# MCU.net
KiCad netlist of a schematic drawn in Altium Designer
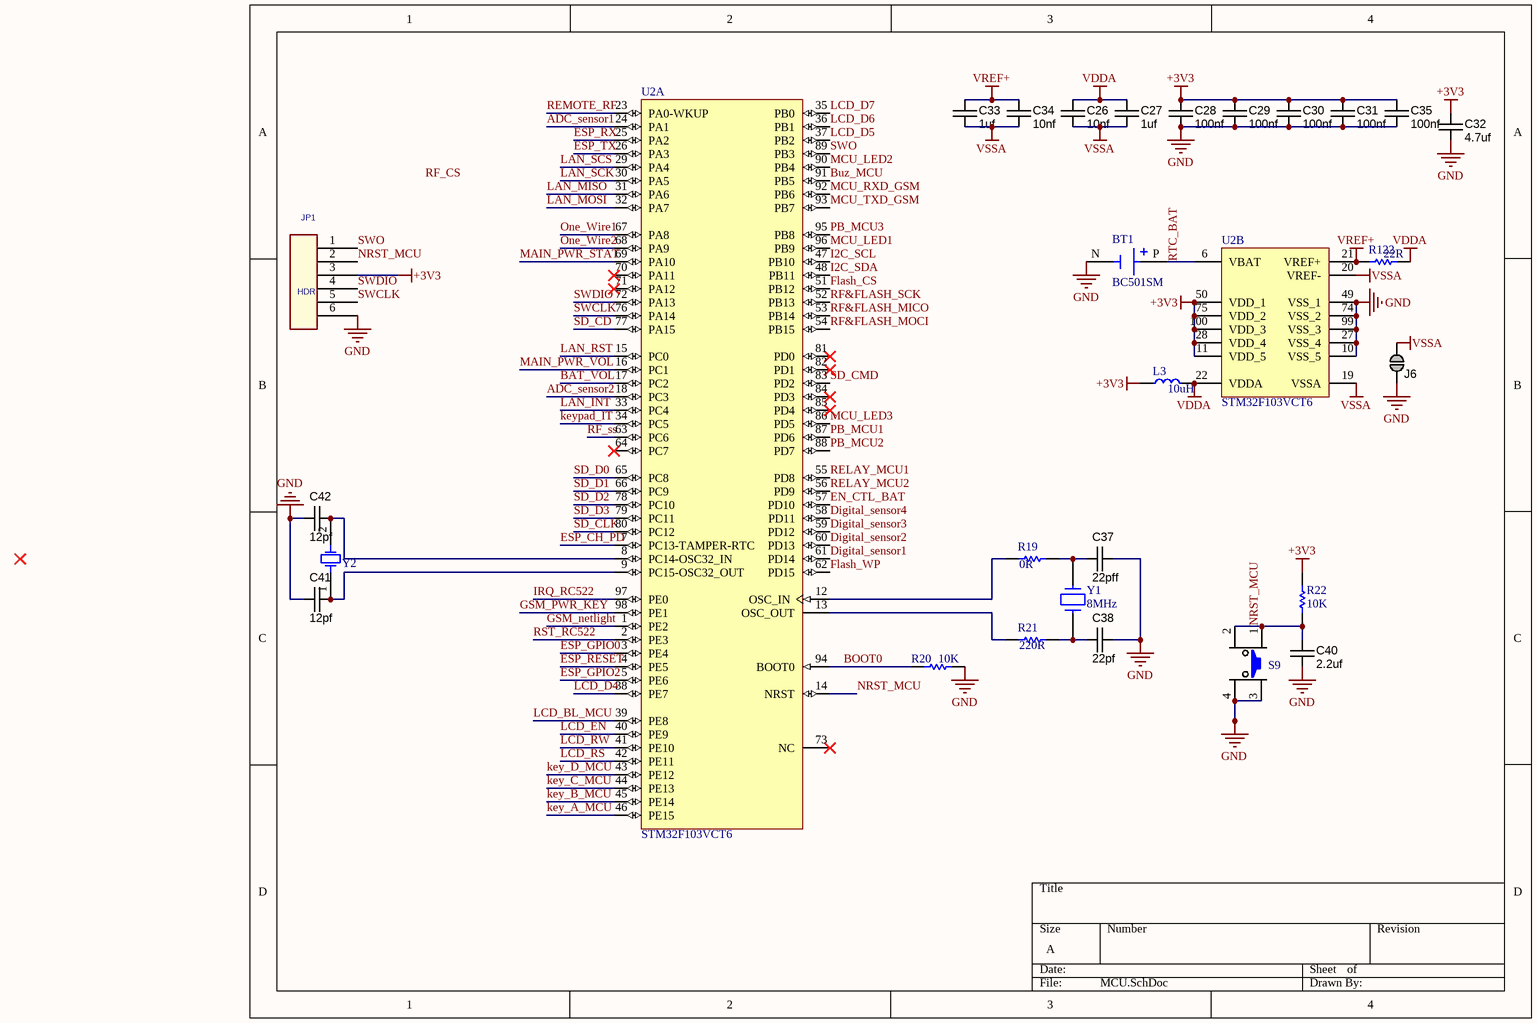
[diagram p0: MCU.SchDoc]

(export (version "E")
  (design (tool "Eeschema 10.0.6"))
  (components
    (comp (ref "BT1")
      (value "BC501SM")
      (footprint "BAT_BC501SM")
      (description "BATTERY HOLDER COIN 12MM SMD")
      (fields (field (name "MF") "MPD"))
      (libsource (lib "altium-import") (part "root_0_mirrored_BC501SM_"))
    )
    (comp (ref "C26")
      (value "10nf")
      (footprint "CAPC1608X90N")
      (description "Capacitor SMD Cer 100nF 10% 50V X7R 0603")
      (fields (field (name "TOLERANCE") "±10%"))
      (libsource (lib "altium-import") (part "root_2_CAPC_100n_0603_X7R_50V_10%_"))
    )
    (comp (ref "C27")
      (value "1uf")
      (footprint "CAPC1608X90N")
      (description "Capacitor SMD Cer 100nF 10% 50V X7R 0603")
      (fields (field (name "TOLERANCE") "±10%"))
      (libsource (lib "altium-import") (part "root_2_CAPC_100n_0603_X7R_50V_10%_"))
    )
    (comp (ref "C28")
      (value "100nf")
      (footprint "CAPC1608X90N")
      (description "Capacitor SMD Cer 100nF 10% 50V X7R 0603")
      (fields (field (name "TOLERANCE") "±10%"))
      (libsource (lib "altium-import") (part "root_2_CAPC_100n_0603_X7R_50V_10%_"))
    )
    (comp (ref "C29")
      (value "100nf")
      (footprint "CAPC1608X90N")
      (description "Capacitor SMD Cer 100nF 10% 50V X7R 0603")
      (fields (field (name "TOLERANCE") "±10%"))
      (libsource (lib "altium-import") (part "root_2_CAPC_100n_0603_X7R_50V_10%_"))
    )
    (comp (ref "C30")
      (value "100nf")
      (footprint "CAPC1608X90N")
      (description "Capacitor SMD Cer 100nF 10% 50V X7R 0603")
      (fields (field (name "TOLERANCE") "±10%"))
      (libsource (lib "altium-import") (part "root_2_CAPC_100n_0603_X7R_50V_10%_"))
    )
    (comp (ref "C31")
      (value "100nf")
      (footprint "CAPC1608X90N")
      (description "Capacitor SMD Cer 100nF 10% 50V X7R 0603")
      (fields (field (name "TOLERANCE") "±10%"))
      (libsource (lib "altium-import") (part "root_2_CAPC_100n_0603_X7R_50V_10%_"))
    )
    (comp (ref "C32")
      (value "4.7uf")
      (footprint "CAPC1608X90N")
      (description "Capacitor SMD Cer 100nF 10% 50V X7R 0603")
      (fields (field (name "TOLERANCE") "±10%"))
      (libsource (lib "altium-import") (part "root_2_CAPC_100n_0603_X7R_50V_10%_"))
    )
    (comp (ref "C33")
      (value "1uf")
      (footprint "CAPC1608X90N")
      (description "Capacitor SMD Cer 100nF 10% 50V X7R 0603")
      (fields (field (name "TOLERANCE") "±10%"))
      (libsource (lib "altium-import") (part "root_2_CAPC_100n_0603_X7R_50V_10%_"))
    )
    (comp (ref "C34")
      (value "10nf")
      (footprint "CAPC1608X90N")
      (description "Capacitor SMD Cer 100nF 10% 50V X7R 0603")
      (fields (field (name "TOLERANCE") "±10%"))
      (libsource (lib "altium-import") (part "root_2_CAPC_100n_0603_X7R_50V_10%_"))
    )
    (comp (ref "C35")
      (value "100nf")
      (footprint "CAPC1608X90N")
      (description "Capacitor SMD Cer 100nF 10% 50V X7R 0603")
      (fields (field (name "TOLERANCE") "±10%"))
      (libsource (lib "altium-import") (part "root_2_CAPC_100n_0603_X7R_50V_10%_"))
    )
    (comp (ref "C37")
      (value "22pff")
      (footprint "CAPC1608X90N")
      (description "Capacitor SMD Cer 100nF 10% 50V X7R 0603")
      (fields (field (name "TOLERANCE") "±10%"))
      (libsource (lib "altium-import") (part "root_1_CAPC_100n_0603_X7R_50V_10%_"))
    )
    (comp (ref "C38")
      (value "22pf")
      (footprint "CAPC1608X90N")
      (description "Capacitor SMD Cer 100nF 10% 50V X7R 0603")
      (fields (field (name "TOLERANCE") "±10%"))
      (libsource (lib "altium-import") (part "root_1_CAPC_100n_0603_X7R_50V_10%_"))
    )
    (comp (ref "C40")
      (value "2.2uf")
      (footprint "CAPC1608X90N")
      (description "Capacitor SMD Cer 100nF 10% 50V X7R 0603")
      (fields (field (name "TOLERANCE") "±10%"))
      (libsource (lib "altium-import") (part "root_0_CAPC_100n_0603_X7R_50V_10%_"))
    )
    (comp (ref "C41")
      (value "12pf")
      (footprint "CAPC1608X90N")
      (description "Capacitor SMD Cer 100nF 10% 50V X7R 0603")
      (fields (field (name "TOLERANCE") "±10%"))
      (libsource (lib "altium-import") (part "root_1_mirrored_CAPC_100n_0603_X7R_50V_10%_"))
    )
    (comp (ref "C42")
      (value "12pf")
      (footprint "CAPC1608X90N")
      (description "Capacitor SMD Cer 100nF 10% 50V X7R 0603")
      (fields (field (name "TOLERANCE") "±10%"))
      (libsource (lib "altium-import") (part "root_1_mirrored_CAPC_100n_0603_X7R_50V_10%_"))
    )
    (comp (ref "J6")
      (value "Jumper")
      (footprint "JUMP1")
      (description "SMD jumper")
      (libsource (lib "Utiliti_Library") (part "JUMP1"))
    )
    (comp (ref "JP1")
      (value "HDR")
      (footprint "HDR_1x6")
      (description "header or jumper box")
      (fields (field (name "DESIGNER") "ABBAS BASEREH"))
      (libsource (lib "altium-import") (part "root_0_mirrored_Header 1x6_"))
    )
    (comp (ref "L3")
      (value "10uH")
      (footprint "L0805")
      (description "Inductor SMD NC 0805")
      (libsource (lib "altium-import") (part "root_0_Inductor SMD NC 0805_"))
    )
    (comp (ref "R19")
      (value "0R")
      (footprint "Resistor_SMD_0603 (1608)")
      (description "Resistor 0603")
      (fields (field (name "PUBLISHER") "Seyed Razi Vesali") (field (name "EMAIL") "razi.vesali@gmail.com"))
      (libsource (lib "resistors") (part "Resistor"))
    )
    (comp (ref "R20")
      (value "10K")
      (footprint "Resistor_SMD_0603 (1608)")
      (description "Resistor 0603")
      (fields (field (name "PUBLISHER") "Seyed Razi Vesali") (field (name "EMAIL") "razi.vesali@gmail.com"))
      (libsource (lib "resistors") (part "Resistor"))
    )
    (comp (ref "R21")
      (value "220R")
      (footprint "Resistor_SMD_0603 (1608)")
      (description "Resistor 0603")
      (fields (field (name "PUBLISHER") "Seyed Razi Vesali") (field (name "EMAIL") "razi.vesali@gmail.com"))
      (libsource (lib "resistors") (part "Resistor"))
    )
    (comp (ref "R22")
      (value "10K")
      (footprint "Resistor_SMD_0603 (1608)")
      (description "Resistor 0603")
      (fields (field (name "PUBLISHER") "Seyed Razi Vesali") (field (name "EMAIL") "razi.vesali@gmail.com"))
      (libsource (lib "resistors") (part "Resistor"))
    )
    (comp (ref "R122")
      (value "22R")
      (footprint "Resistor_SMD_0603 (1608)")
      (description "Resistor 0603")
      (fields (field (name "PUBLISHER") "Seyed Razi Vesali") (field (name "EMAIL") "razi.vesali@gmail.com"))
      (libsource (lib "resistors") (part "Resistor"))
    )
    (comp (ref "S9")
      (value "SW_PB4 SMD")
      (footprint "SMD_PB")
      (libsource (lib "Micro Switch") (part "SW_PB4 SMD"))
    )
    (comp (ref "U2")
      (value "STM32F103VCT6")
      (footprint "STM-LQFP100_L")
      (libsource (lib "altium-import") (part "root_0_STM32F103VCT6_"))
    )
    (comp (ref "Y1")
      (value "8MHz")
      (footprint "My_Crystal - SMD")
      (description "Crystal")
      (libsource (lib "altium-import") (part "root_1_CRYSTAL_SMD_"))
    )
    (comp (ref "Y2")
      (value "32.768KHz")
      (footprint "Crystal Clock RIGHT 3")
      (description "Crystal")
      (libsource (lib "altium-import") (part "root_1_mirrored_Crystal RTC_"))
    )
  )
  (nets
    (net (code "1") (name "+3V3") (class "Default")
      (node (ref "C28") (pin "2") (pintype "passive"))
      (node (ref "C29") (pin "2") (pintype "passive"))
      (node (ref "C30") (pin "2") (pintype "passive"))
      (node (ref "C31") (pin "2") (pintype "passive"))
      (node (ref "C32") (pin "2") (pintype "passive"))
      (node (ref "C35") (pin "2") (pintype "passive"))
      (node (ref "JP1") (pin "3") (pinfunction "3_3") (pintype "passive"))
      (node (ref "L3") (pin "1") (pinfunction "1_1") (pintype "passive"))
      (node (ref "R22") (pin "1") (pinfunction "1_1") (pintype "passive"))
      (node (ref "U2") (pin "100") (pinfunction "VDD_3_100") (pintype "power_in"))
      (node (ref "U2") (pin "11") (pinfunction "VDD_5_11") (pintype "power_in"))
      (node (ref "U2") (pin "28") (pinfunction "VDD_4_28") (pintype "power_in"))
      (node (ref "U2") (pin "50") (pinfunction "VDD_1_50") (pintype "power_in"))
      (node (ref "U2") (pin "75") (pinfunction "VDD_2_75") (pintype "power_in"))
    )
    (net (code "2") (name "/ADC_sensor1") (class "Default")
      (node (ref "U2") (pin "24") (pinfunction "PA1_24") (pintype "bidirectional"))
    )
    (net (code "3") (name "/ADC_sensor2") (class "Default")
      (node (ref "U2") (pin "18") (pinfunction "PC3_18") (pintype "bidirectional"))
    )
    (net (code "4") (name "/BAT_VOL") (class "Default")
      (node (ref "U2") (pin "17") (pinfunction "PC2_17") (pintype "bidirectional"))
    )
    (net (code "5") (name "/BOOT0") (class "Default")
      (node (ref "R20") (pin "1") (pinfunction "1_1") (pintype "passive"))
      (node (ref "U2") (pin "94") (pinfunction "BOOT0_94") (pintype "input"))
    )
    (net (code "6") (name "/Buz_MCU") (class "Default")
      (node (ref "U2") (pin "91") (pinfunction "PB5_91") (pintype "bidirectional"))
    )
    (net (code "7") (name "/Digital_sensor1") (class "Default")
      (node (ref "U2") (pin "61") (pinfunction "PD14_61") (pintype "bidirectional"))
    )
    (net (code "8") (name "/Digital_sensor2") (class "Default")
      (node (ref "U2") (pin "60") (pinfunction "PD13_60") (pintype "bidirectional"))
    )
    (net (code "9") (name "/Digital_sensor3") (class "Default")
      (node (ref "U2") (pin "59") (pinfunction "PD12_59") (pintype "bidirectional"))
    )
    (net (code "10") (name "/Digital_sensor4") (class "Default")
      (node (ref "U2") (pin "58") (pinfunction "PD11_58") (pintype "bidirectional"))
    )
    (net (code "11") (name "/EN_CTL_BAT") (class "Default")
      (node (ref "U2") (pin "57") (pinfunction "PD10_57") (pintype "bidirectional"))
    )
    (net (code "12") (name "/ESP_CH_PD") (class "Default")
      (node (ref "U2") (pin "7") (pinfunction "PC13-TAMPER-RTC_7") (pintype "bidirectional"))
    )
    (net (code "13") (name "/ESP_GPIO0") (class "Default")
      (node (ref "U2") (pin "3") (pinfunction "PE4_3") (pintype "bidirectional"))
    )
    (net (code "14") (name "/ESP_GPIO2") (class "Default")
      (node (ref "U2") (pin "5") (pinfunction "PE6_5") (pintype "bidirectional"))
    )
    (net (code "15") (name "/ESP_RESET") (class "Default")
      (node (ref "U2") (pin "4") (pinfunction "PE5_4") (pintype "bidirectional"))
    )
    (net (code "16") (name "/ESP_RX") (class "Default")
      (node (ref "U2") (pin "25") (pinfunction "PA2_25") (pintype "bidirectional"))
    )
    (net (code "17") (name "/ESP_TX") (class "Default")
      (node (ref "U2") (pin "26") (pinfunction "PA3_26") (pintype "bidirectional"))
    )
    (net (code "18") (name "/Flash_CS") (class "Default")
      (node (ref "U2") (pin "51") (pinfunction "PB12_51") (pintype "bidirectional"))
    )
    (net (code "19") (name "/Flash_WP") (class "Default")
      (node (ref "U2") (pin "62") (pinfunction "PD15_62") (pintype "bidirectional"))
    )
    (net (code "20") (name "/GSM_PWR_KEY") (class "Default")
      (node (ref "U2") (pin "98") (pinfunction "PE1_98") (pintype "bidirectional"))
    )
    (net (code "21") (name "/GSM_netlight") (class "Default")
      (node (ref "U2") (pin "1") (pinfunction "PE2_1") (pintype "bidirectional"))
    )
    (net (code "22") (name "/I2C_SCL") (class "Default")
      (node (ref "U2") (pin "47") (pinfunction "PB10_47") (pintype "bidirectional"))
    )
    (net (code "23") (name "/I2C_SDA") (class "Default")
      (node (ref "U2") (pin "48") (pinfunction "PB11_48") (pintype "bidirectional"))
    )
    (net (code "24") (name "/IRQ_RC522") (class "Default")
      (node (ref "U2") (pin "97") (pinfunction "PE0_97") (pintype "bidirectional"))
    )
    (net (code "25") (name "/LAN_INT") (class "Default")
      (node (ref "U2") (pin "33") (pinfunction "PC4_33") (pintype "bidirectional"))
    )
    (net (code "26") (name "/LAN_MISO") (class "Default")
      (node (ref "U2") (pin "31") (pinfunction "PA6_31") (pintype "bidirectional"))
    )
    (net (code "27") (name "/LAN_MOSI") (class "Default")
      (node (ref "U2") (pin "32") (pinfunction "PA7_32") (pintype "bidirectional"))
    )
    (net (code "28") (name "/LAN_RST") (class "Default")
      (node (ref "U2") (pin "15") (pinfunction "PC0_15") (pintype "bidirectional"))
    )
    (net (code "29") (name "/LAN_SCK") (class "Default")
      (node (ref "U2") (pin "30") (pinfunction "PA5_30") (pintype "bidirectional"))
    )
    (net (code "30") (name "/LAN_SCS") (class "Default")
      (node (ref "U2") (pin "29") (pinfunction "PA4_29") (pintype "bidirectional"))
    )
    (net (code "31") (name "/LCD_BL_MCU") (class "Default")
      (node (ref "U2") (pin "39") (pinfunction "PE8_39") (pintype "bidirectional"))
    )
    (net (code "32") (name "/LCD_D4") (class "Default")
      (node (ref "U2") (pin "38") (pinfunction "PE7_38") (pintype "bidirectional"))
    )
    (net (code "33") (name "/LCD_D5") (class "Default")
      (node (ref "U2") (pin "37") (pinfunction "PB2_37") (pintype "bidirectional"))
    )
    (net (code "34") (name "/LCD_D6") (class "Default")
      (node (ref "U2") (pin "36") (pinfunction "PB1_36") (pintype "bidirectional"))
    )
    (net (code "35") (name "/LCD_D7") (class "Default")
      (node (ref "U2") (pin "35") (pinfunction "PB0_35") (pintype "bidirectional"))
    )
    (net (code "36") (name "/LCD_EN") (class "Default")
      (node (ref "U2") (pin "40") (pinfunction "PE9_40") (pintype "bidirectional"))
    )
    (net (code "37") (name "/LCD_RS") (class "Default")
      (node (ref "U2") (pin "42") (pinfunction "PE11_42") (pintype "bidirectional"))
    )
    (net (code "38") (name "/LCD_RW") (class "Default")
      (node (ref "U2") (pin "41") (pinfunction "PE10_41") (pintype "bidirectional"))
    )
    (net (code "39") (name "/MAIN_PWR_STAT") (class "Default")
      (node (ref "U2") (pin "69") (pinfunction "PA10_69") (pintype "bidirectional"))
    )
    (net (code "40") (name "/MAIN_PWR_VOL") (class "Default")
      (node (ref "U2") (pin "16") (pinfunction "PC1_16") (pintype "bidirectional"))
    )
    (net (code "41") (name "/MCU_LED1") (class "Default")
      (node (ref "U2") (pin "96") (pinfunction "PB9_96") (pintype "bidirectional"))
    )
    (net (code "42") (name "/MCU_LED2") (class "Default")
      (node (ref "U2") (pin "90") (pinfunction "PB4_90") (pintype "bidirectional"))
    )
    (net (code "43") (name "/MCU_LED3") (class "Default")
      (node (ref "U2") (pin "86") (pinfunction "PD5_86") (pintype "bidirectional"))
    )
    (net (code "44") (name "/MCU_RXD_GSM") (class "Default")
      (node (ref "U2") (pin "92") (pinfunction "PB6_92") (pintype "bidirectional"))
    )
    (net (code "45") (name "/MCU_TXD_GSM") (class "Default")
      (node (ref "U2") (pin "93") (pinfunction "PB7_93") (pintype "bidirectional"))
    )
    (net (code "46") (name "/NRST_MCU") (class "Default")
      (node (ref "C40") (pin "1") (pintype "passive"))
      (node (ref "JP1") (pin "2") (pinfunction "2_2") (pintype "passive"))
      (node (ref "R22") (pin "2") (pinfunction "2_2") (pintype "passive"))
      (node (ref "S9") (pin "1") (pinfunction "1_1") (pintype "passive"))
      (node (ref "S9") (pin "2") (pinfunction "2_2") (pintype "passive"))
      (node (ref "U2") (pin "14") (pinfunction "NRST_14") (pintype "bidirectional"))
    )
    (net (code "47") (name "/One_Wire1") (class "Default")
      (node (ref "U2") (pin "67") (pinfunction "PA8_67") (pintype "bidirectional"))
    )
    (net (code "48") (name "/One_Wire2") (class "Default")
      (node (ref "U2") (pin "68") (pinfunction "PA9_68") (pintype "bidirectional"))
    )
    (net (code "49") (name "/PB_MCU1") (class "Default")
      (node (ref "U2") (pin "87") (pinfunction "PD6_87") (pintype "bidirectional"))
    )
    (net (code "50") (name "/PB_MCU2") (class "Default")
      (node (ref "U2") (pin "88") (pinfunction "PD7_88") (pintype "bidirectional"))
    )
    (net (code "51") (name "/PB_MCU3") (class "Default")
      (node (ref "U2") (pin "95") (pinfunction "PB8_95") (pintype "bidirectional"))
    )
    (net (code "52") (name "/RELAY_MCU1") (class "Default")
      (node (ref "U2") (pin "55") (pinfunction "PD8_55") (pintype "bidirectional"))
    )
    (net (code "53") (name "/RELAY_MCU2") (class "Default")
      (node (ref "U2") (pin "56") (pinfunction "PD9_56") (pintype "bidirectional"))
    )
    (net (code "54") (name "/REMOTE_RF") (class "Default")
      (node (ref "U2") (pin "23") (pinfunction "PA0-WKUP_23") (pintype "bidirectional"))
    )
    (net (code "55") (name "/RF&FLASH_MICO") (class "Default")
      (node (ref "U2") (pin "53") (pinfunction "PB14_53") (pintype "bidirectional"))
    )
    (net (code "56") (name "/RF&FLASH_MOCI") (class "Default")
      (node (ref "U2") (pin "54") (pinfunction "PB15_54") (pintype "bidirectional"))
    )
    (net (code "57") (name "/RF&FLASH_SCK") (class "Default")
      (node (ref "U2") (pin "52") (pinfunction "PB13_52") (pintype "bidirectional"))
    )
    (net (code "59") (name "/RF_ss") (class "Default")
      (node (ref "U2") (pin "63") (pinfunction "PC6_63") (pintype "bidirectional"))
    )
    (net (code "60") (name "/RST_RC522") (class "Default")
      (node (ref "U2") (pin "2") (pinfunction "PE3_2") (pintype "bidirectional"))
    )
    (net (code "61") (name "/RTC_BAT") (class "Default")
      (node (ref "BT1") (pin "P") (pinfunction "POS_P") (pintype "passive"))
      (node (ref "U2") (pin "6") (pinfunction "VBAT_6") (pintype "power_in"))
    )
    (net (code "62") (name "/SD_CD") (class "Default")
      (node (ref "U2") (pin "77") (pinfunction "PA15_77") (pintype "bidirectional"))
    )
    (net (code "63") (name "/SD_CLK") (class "Default")
      (node (ref "U2") (pin "80") (pinfunction "PC12_80") (pintype "bidirectional"))
    )
    (net (code "64") (name "/SD_CMD") (class "Default")
      (node (ref "U2") (pin "83") (pinfunction "PD2_83") (pintype "bidirectional"))
    )
    (net (code "65") (name "/SD_D0") (class "Default")
      (node (ref "U2") (pin "65") (pinfunction "PC8_65") (pintype "bidirectional"))
    )
    (net (code "66") (name "/SD_D1") (class "Default")
      (node (ref "U2") (pin "66") (pinfunction "PC9_66") (pintype "bidirectional"))
    )
    (net (code "67") (name "/SD_D2") (class "Default")
      (node (ref "U2") (pin "78") (pinfunction "PC10_78") (pintype "bidirectional"))
    )
    (net (code "68") (name "/SD_D3") (class "Default")
      (node (ref "U2") (pin "79") (pinfunction "PC11_79") (pintype "bidirectional"))
    )
    (net (code "69") (name "/SWCLK") (class "Default")
      (node (ref "JP1") (pin "5") (pinfunction "5_5") (pintype "passive"))
      (node (ref "U2") (pin "76") (pinfunction "PA14_76") (pintype "bidirectional"))
    )
    (net (code "70") (name "/SWDIO") (class "Default")
      (node (ref "JP1") (pin "4") (pinfunction "4_4") (pintype "passive"))
      (node (ref "U2") (pin "72") (pinfunction "PA13_72") (pintype "bidirectional"))
    )
    (net (code "71") (name "/SWO") (class "Default")
      (node (ref "JP1") (pin "1") (pinfunction "1_1") (pintype "passive"))
      (node (ref "U2") (pin "89") (pinfunction "PB3_89") (pintype "bidirectional"))
    )
    (net (code "72") (name "/key_A_MCU") (class "Default")
      (node (ref "U2") (pin "46") (pinfunction "PE15_46") (pintype "bidirectional"))
    )
    (net (code "73") (name "/key_B_MCU") (class "Default")
      (node (ref "U2") (pin "45") (pinfunction "PE14_45") (pintype "bidirectional"))
    )
    (net (code "74") (name "/key_C_MCU") (class "Default")
      (node (ref "U2") (pin "44") (pinfunction "PE13_44") (pintype "bidirectional"))
    )
    (net (code "75") (name "/key_D_MCU") (class "Default")
      (node (ref "U2") (pin "43") (pinfunction "PE12_43") (pintype "bidirectional"))
    )
    (net (code "76") (name "/keypad_IT") (class "Default")
      (node (ref "U2") (pin "34") (pinfunction "PC5_34") (pintype "bidirectional"))
    )
    (net (code "77") (name "GND") (class "Default")
      (node (ref "BT1") (pin "N") (pinfunction "NEG_N") (pintype "passive"))
      (node (ref "C28") (pin "1") (pintype "passive"))
      (node (ref "C29") (pin "1") (pintype "passive"))
      (node (ref "C30") (pin "1") (pintype "passive"))
      (node (ref "C31") (pin "1") (pintype "passive"))
      (node (ref "C32") (pin "1") (pintype "passive"))
      (node (ref "C35") (pin "1") (pintype "passive"))
      (node (ref "C37") (pin "2") (pintype "passive"))
      (node (ref "C38") (pin "2") (pintype "passive"))
      (node (ref "C40") (pin "2") (pintype "passive"))
      (node (ref "C41") (pin "2") (pintype "passive"))
      (node (ref "C42") (pin "2") (pintype "passive"))
      (node (ref "J6") (pin "1") (pintype "passive"))
      (node (ref "JP1") (pin "6") (pinfunction "6_6") (pintype "passive"))
      (node (ref "R20") (pin "2") (pinfunction "2_2") (pintype "passive"))
      (node (ref "S9") (pin "3") (pinfunction "3_3") (pintype "passive"))
      (node (ref "S9") (pin "4") (pinfunction "4_4") (pintype "passive"))
      (node (ref "U2") (pin "10") (pinfunction "VSS_5_10") (pintype "power_in"))
      (node (ref "U2") (pin "27") (pinfunction "VSS_4_27") (pintype "power_in"))
      (node (ref "U2") (pin "49") (pinfunction "VSS_1_49") (pintype "power_in"))
      (node (ref "U2") (pin "74") (pinfunction "VSS_2_74") (pintype "power_in"))
      (node (ref "U2") (pin "99") (pinfunction "VSS_3_99") (pintype "power_in"))
    )
    (net (code "78") (name "Net-(C37-Pad1)") (class "Default")
      (node (ref "C37") (pin "1") (pintype "passive"))
      (node (ref "R19") (pin "2") (pinfunction "2_2") (pintype "passive"))
      (node (ref "Y1") (pin "2") (pinfunction "2_2") (pintype "passive"))
    )
    (net (code "79") (name "Net-(C38-Pad1)") (class "Default")
      (node (ref "C38") (pin "1") (pintype "passive"))
      (node (ref "R21") (pin "2") (pinfunction "2_2") (pintype "passive"))
      (node (ref "Y1") (pin "1") (pinfunction "1_1") (pintype "passive"))
    )
    (net (code "80") (name "Net-(U2A-OSC_IN)") (class "Default")
      (node (ref "R19") (pin "1") (pinfunction "1_1") (pintype "passive"))
      (node (ref "U2") (pin "12") (pinfunction "OSC_IN_12") (pintype "input"))
    )
    (net (code "81") (name "Net-(U2A-OSC_OUT)") (class "Default")
      (node (ref "R21") (pin "1") (pinfunction "1_1") (pintype "passive"))
      (node (ref "U2") (pin "13") (pinfunction "OSC_OUT_13") (pintype "passive"))
    )
    (net (code "82") (name "Net-(U2A-PC14-OSC32_IN)") (class "Default")
      (node (ref "C42") (pin "1") (pintype "passive"))
      (node (ref "U2") (pin "8") (pinfunction "PC14-OSC32_IN_8") (pintype "bidirectional"))
      (node (ref "Y2") (pin "2") (pinfunction "2_2") (pintype "passive"))
    )
    (net (code "83") (name "Net-(U2A-PC15-OSC32_OUT)") (class "Default")
      (node (ref "C41") (pin "1") (pintype "passive"))
      (node (ref "U2") (pin "9") (pinfunction "PC15-OSC32_OUT_9") (pintype "bidirectional"))
      (node (ref "Y2") (pin "1") (pinfunction "1_1") (pintype "passive"))
    )
    (net (code "84") (name "VDDA") (class "Default")
      (node (ref "C26") (pin "2") (pintype "passive"))
      (node (ref "C27") (pin "2") (pintype "passive"))
      (node (ref "L3") (pin "2") (pinfunction "2_2") (pintype "passive"))
      (node (ref "R122") (pin "1") (pinfunction "1_1") (pintype "passive"))
      (node (ref "U2") (pin "22") (pinfunction "VDDA_22") (pintype "power_in"))
    )
    (net (code "85") (name "VREF+") (class "Default")
      (node (ref "C33") (pin "2") (pintype "passive"))
      (node (ref "C34") (pin "2") (pintype "passive"))
      (node (ref "R122") (pin "2") (pinfunction "2_2") (pintype "passive"))
      (node (ref "U2") (pin "21") (pinfunction "VREF+_21") (pintype "power_in"))
    )
    (net (code "86") (name "VSSA") (class "Default")
      (node (ref "C26") (pin "1") (pintype "passive"))
      (node (ref "C27") (pin "1") (pintype "passive"))
      (node (ref "C33") (pin "1") (pintype "passive"))
      (node (ref "C34") (pin "1") (pintype "passive"))
      (node (ref "J6") (pin "2") (pintype "passive"))
      (node (ref "U2") (pin "19") (pinfunction "VSSA_19") (pintype "power_in"))
      (node (ref "U2") (pin "20") (pinfunction "VREF-_20") (pintype "power_in"))
    )
    (net (code "87") (name "unconnected-(U2A-NC-Pad73)") (class "Default")
      (node (ref "U2") (pin "73") (pinfunction "NC_73") (pintype "passive+no_connect"))
    )
    (net (code "88") (name "unconnected-(U2A-PA11-Pad70)") (class "Default")
      (node (ref "U2") (pin "70") (pinfunction "PA11_70") (pintype "bidirectional+no_connect"))
    )
    (net (code "89") (name "unconnected-(U2A-PA12-Pad71)") (class "Default")
      (node (ref "U2") (pin "71") (pinfunction "PA12_71") (pintype "bidirectional+no_connect"))
    )
    (net (code "90") (name "unconnected-(U2A-PC7-Pad64)") (class "Default")
      (node (ref "U2") (pin "64") (pinfunction "PC7_64") (pintype "bidirectional+no_connect"))
    )
    (net (code "91") (name "unconnected-(U2A-PD0-Pad81)") (class "Default")
      (node (ref "U2") (pin "81") (pinfunction "PD0_81") (pintype "bidirectional+no_connect"))
    )
    (net (code "92") (name "unconnected-(U2A-PD1-Pad82)") (class "Default")
      (node (ref "U2") (pin "82") (pinfunction "PD1_82") (pintype "bidirectional+no_connect"))
    )
    (net (code "93") (name "unconnected-(U2A-PD3-Pad84)") (class "Default")
      (node (ref "U2") (pin "84") (pinfunction "PD3_84") (pintype "bidirectional+no_connect"))
    )
    (net (code "94") (name "unconnected-(U2A-PD4-Pad85)") (class "Default")
      (node (ref "U2") (pin "85") (pinfunction "PD4_85") (pintype "bidirectional+no_connect"))
    )
  )
)
